# board.net
KiCad netlist of a schematic drawn in EAGLE
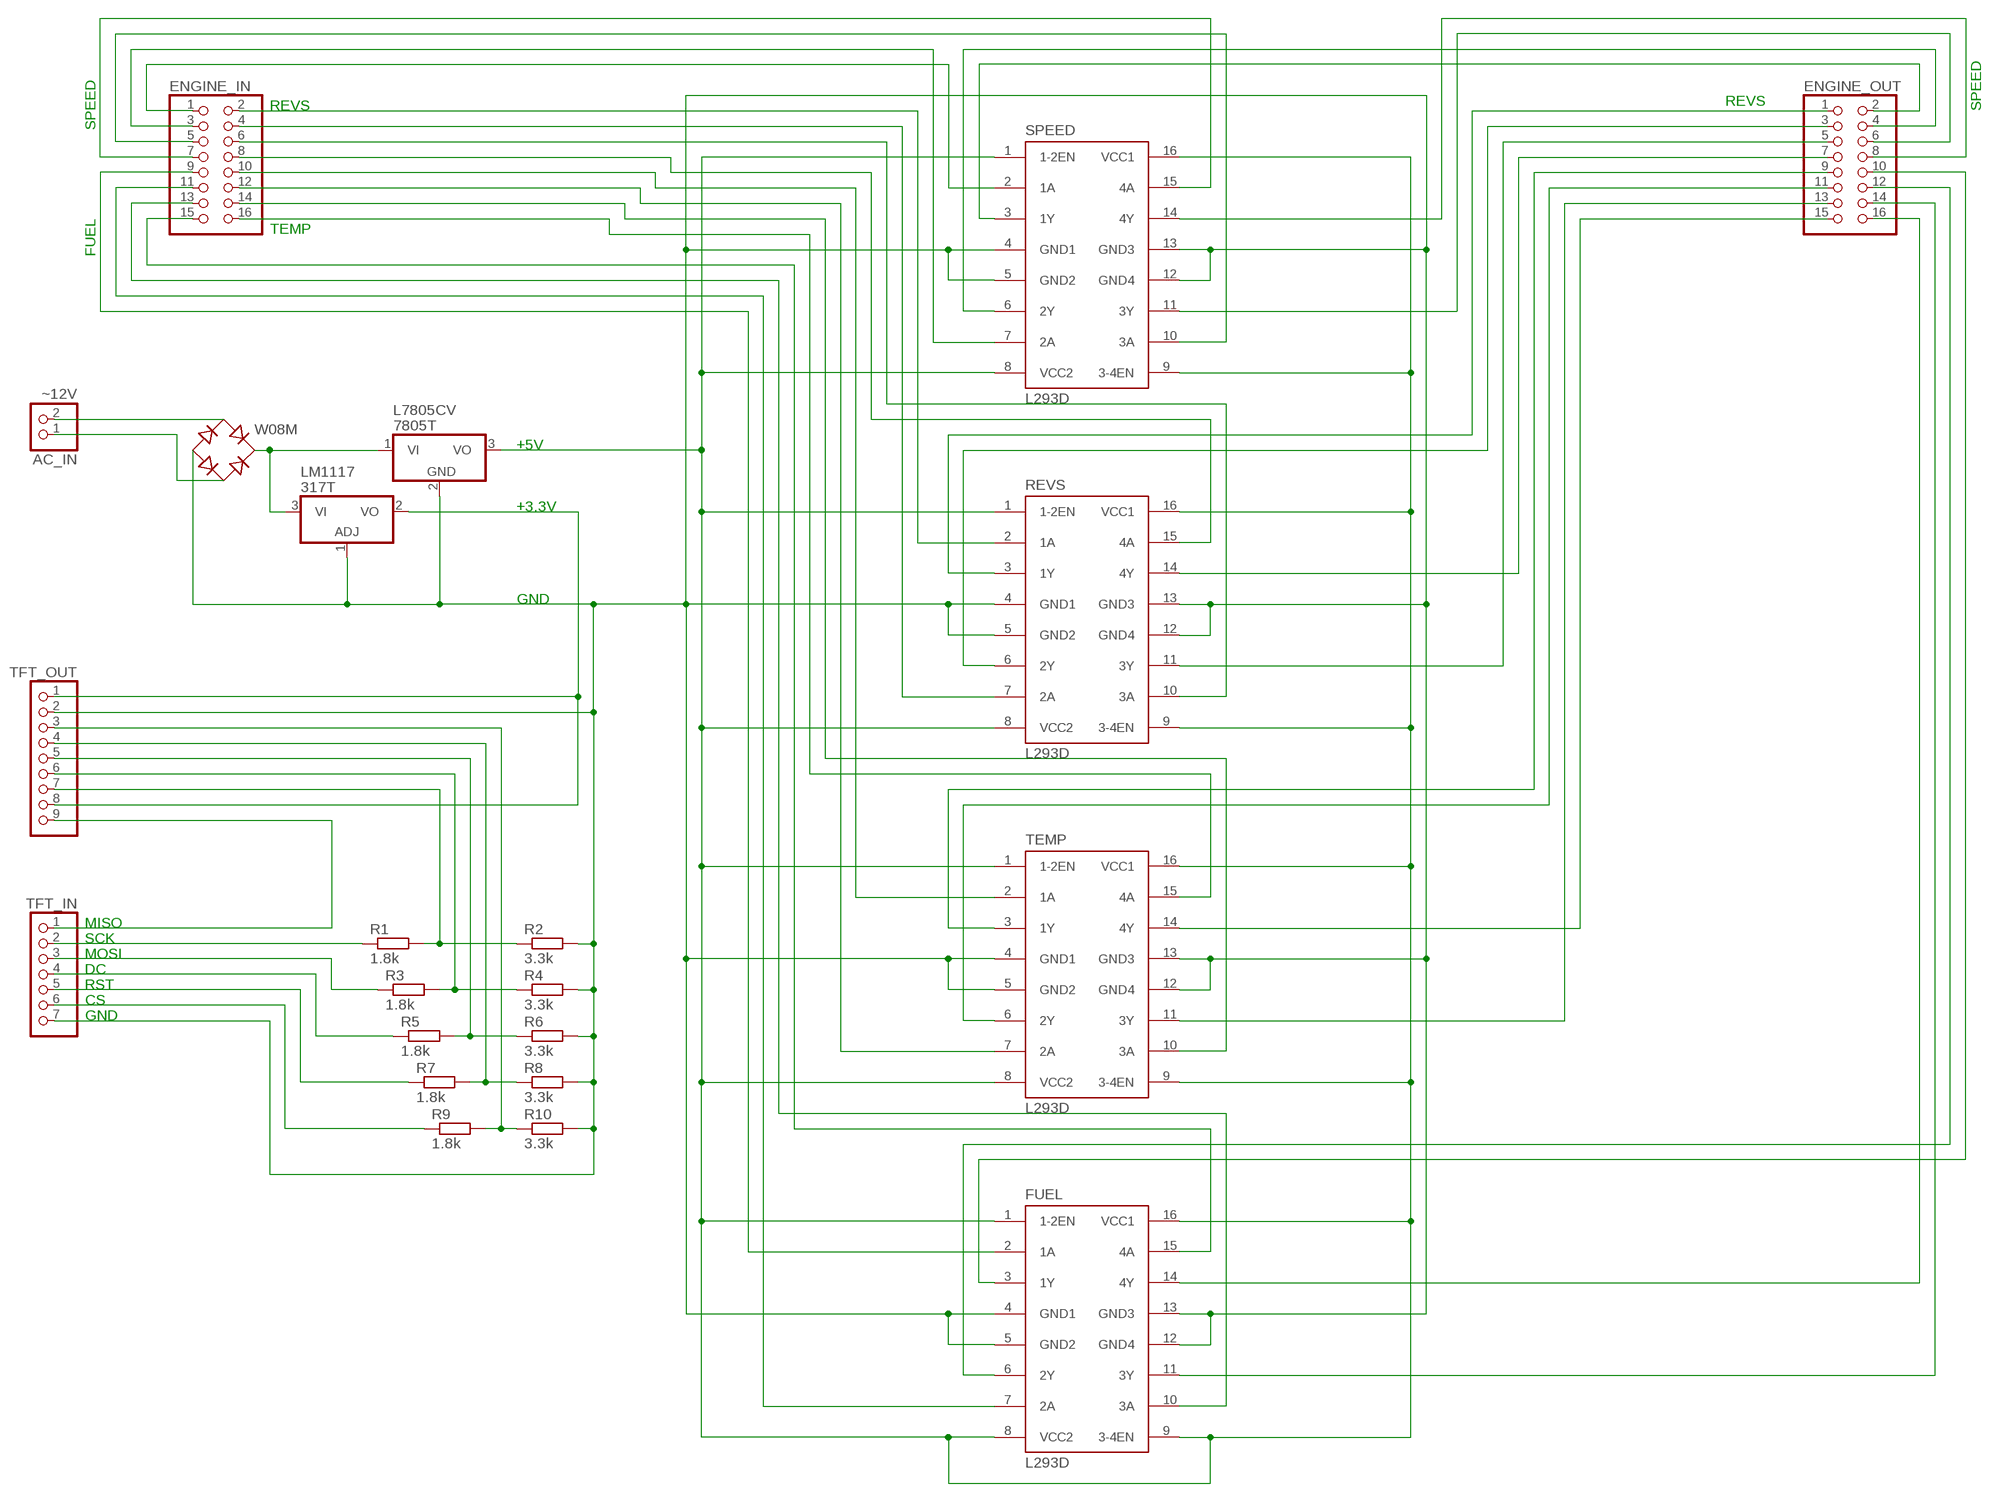
[diagram p0: schematic, sheet 1]

(export (version "E")
  (design (tool "Eeschema 10.0.6"))
  (components
    (comp (ref "AC_IN")
      (value "~12V")
      (footprint "eagle-import:1X02")
      (libsource (lib "eagle-import") (part "PINHD-1X2"))
    )
    (comp (ref "ENGINE_IN")
      (value "PINHD-2X8")
      (footprint "eagle-import:2X08")
      (libsource (lib "eagle-import") (part "PINHD-2X8"))
    )
    (comp (ref "ENGINE_OUT")
      (value "PINHD-2X8")
      (footprint "eagle-import:2X08")
      (libsource (lib "eagle-import") (part "PINHD-2X8"))
    )
    (comp (ref "FUEL")
      (value "L293D")
      (footprint "eagle-import:DIL16")
      (libsource (lib "eagle-import") (part "L293D"))
    )
    (comp (ref "L7805CV")
      (value "7805T")
      (footprint "eagle-import:TO220H")
      (libsource (lib "eagle-import") (part "78T05"))
    )
    (comp (ref "LM1117")
      (value "317T")
      (footprint "eagle-import:TO220H")
      (libsource (lib "eagle-import") (part "317T"))
    )
    (comp (ref "R1")
      (value "1.8k")
      (footprint "eagle-import:0309_12")
      (libsource (lib "eagle-import") (part "R-EU_0309/12"))
    )
    (comp (ref "R2")
      (value "3.3k")
      (footprint "eagle-import:0309_12")
      (libsource (lib "eagle-import") (part "R-EU_0309/12"))
    )
    (comp (ref "R3")
      (value "1.8k")
      (footprint "eagle-import:0309_12")
      (libsource (lib "eagle-import") (part "R-EU_0309/12"))
    )
    (comp (ref "R4")
      (value "3.3k")
      (footprint "eagle-import:0309_12")
      (libsource (lib "eagle-import") (part "R-EU_0309/12"))
    )
    (comp (ref "R5")
      (value "1.8k")
      (footprint "eagle-import:0309_12")
      (libsource (lib "eagle-import") (part "R-EU_0309/12"))
    )
    (comp (ref "R6")
      (value "3.3k")
      (footprint "eagle-import:0309_12")
      (libsource (lib "eagle-import") (part "R-EU_0309/12"))
    )
    (comp (ref "R7")
      (value "1.8k")
      (footprint "eagle-import:0309_12")
      (libsource (lib "eagle-import") (part "R-EU_0309/12"))
    )
    (comp (ref "R8")
      (value "3.3k")
      (footprint "eagle-import:0309_12")
      (libsource (lib "eagle-import") (part "R-EU_0309/12"))
    )
    (comp (ref "R9")
      (value "1.8k")
      (footprint "eagle-import:0309_12")
      (libsource (lib "eagle-import") (part "R-EU_0309/12"))
    )
    (comp (ref "R10")
      (value "3.3k")
      (footprint "eagle-import:0309_12")
      (libsource (lib "eagle-import") (part "R-EU_0309/12"))
    )
    (comp (ref "REVS")
      (value "L293D")
      (footprint "eagle-import:DIL16")
      (libsource (lib "eagle-import") (part "L293D"))
    )
    (comp (ref "SPEED")
      (value "L293D")
      (footprint "eagle-import:DIL16")
      (libsource (lib "eagle-import") (part "L293D"))
    )
    (comp (ref "TEMP")
      (value "L293D")
      (footprint "eagle-import:DIL16")
      (libsource (lib "eagle-import") (part "L293D"))
    )
    (comp (ref "TFT_IN")
      (value "PINHD-1X7")
      (footprint "eagle-import:1X07")
      (libsource (lib "eagle-import") (part "PINHD-1X7"))
    )
    (comp (ref "TFT_OUT")
      (value "PINHD-1X9")
      (footprint "eagle-import:1X09")
      (libsource (lib "eagle-import") (part "PINHD-1X9"))
    )
    (comp (ref "W08M")
      (value "RB1A")
      (footprint "eagle-import:RB1A")
      (libsource (lib "eagle-import") (part "RB1A"))
    )
  )
  (nets
    (net (code "1") (name "Net-(AC_IN-Pad1)") (class "Default")
      (node (ref "AC_IN") (pin "1") (pinfunction "1_1") (pintype "passive"))
      (node (ref "W08M") (pin "AC2") (pinfunction "AC2_AC2") (pintype "passive"))
    )
    (net (code "2") (name "Net-(AC_IN-Pad2)") (class "Default")
      (node (ref "AC_IN") (pin "2") (pinfunction "2_2") (pintype "passive"))
      (node (ref "W08M") (pin "AC1") (pinfunction "AC1_AC1") (pintype "passive"))
    )
    (net (code "3") (name "Net-(FUEL-1-2EN)") (class "Default")
      (node (ref "FUEL") (pin "1") (pinfunction "1-2EN_1") (pintype "input"))
      (node (ref "FUEL") (pin "16") (pinfunction "VCC1_16") (pintype "power_in"))
      (node (ref "FUEL") (pin "8") (pinfunction "VCC2_8") (pintype "power_in"))
      (node (ref "FUEL") (pin "9") (pinfunction "3-4EN_9") (pintype "input"))
      (node (ref "L7805CV") (pin "3") (pinfunction "VO_3") (pintype "passive"))
      (node (ref "REVS") (pin "1") (pinfunction "1-2EN_1") (pintype "input"))
      (node (ref "REVS") (pin "16") (pinfunction "VCC1_16") (pintype "power_in"))
      (node (ref "REVS") (pin "8") (pinfunction "VCC2_8") (pintype "power_in"))
      (node (ref "REVS") (pin "9") (pinfunction "3-4EN_9") (pintype "input"))
      (node (ref "SPEED") (pin "1") (pinfunction "1-2EN_1") (pintype "input"))
      (node (ref "SPEED") (pin "16") (pinfunction "VCC1_16") (pintype "power_in"))
      (node (ref "SPEED") (pin "8") (pinfunction "VCC2_8") (pintype "power_in"))
      (node (ref "SPEED") (pin "9") (pinfunction "3-4EN_9") (pintype "input"))
      (node (ref "TEMP") (pin "1") (pinfunction "1-2EN_1") (pintype "input"))
      (node (ref "TEMP") (pin "16") (pinfunction "VCC1_16") (pintype "power_in"))
      (node (ref "TEMP") (pin "8") (pinfunction "VCC2_8") (pintype "power_in"))
      (node (ref "TEMP") (pin "9") (pinfunction "3-4EN_9") (pintype "input"))
    )
    (net (code "4") (name "Net-(FUEL-1A)") (class "Default")
      (node (ref "ENGINE_IN") (pin "9") (pinfunction "9_9") (pintype "passive"))
      (node (ref "FUEL") (pin "2") (pinfunction "1A_2") (pintype "input"))
    )
    (net (code "5") (name "Net-(FUEL-1Y)") (class "Default")
      (node (ref "ENGINE_OUT") (pin "10") (pinfunction "10_10") (pintype "passive"))
      (node (ref "FUEL") (pin "3") (pinfunction "1Y_3") (pintype "output"))
    )
    (net (code "6") (name "Net-(FUEL-2A)") (class "Default")
      (node (ref "ENGINE_IN") (pin "11") (pinfunction "11_11") (pintype "passive"))
      (node (ref "FUEL") (pin "7") (pinfunction "2A_7") (pintype "input"))
    )
    (net (code "7") (name "Net-(FUEL-2Y)") (class "Default")
      (node (ref "ENGINE_OUT") (pin "12") (pinfunction "12_12") (pintype "passive"))
      (node (ref "FUEL") (pin "6") (pinfunction "2Y_6") (pintype "output"))
    )
    (net (code "8") (name "Net-(FUEL-3A)") (class "Default")
      (node (ref "ENGINE_IN") (pin "13") (pinfunction "13_13") (pintype "passive"))
      (node (ref "FUEL") (pin "10") (pinfunction "3A_10") (pintype "input"))
    )
    (net (code "9") (name "Net-(FUEL-3Y)") (class "Default")
      (node (ref "ENGINE_OUT") (pin "14") (pinfunction "14_14") (pintype "passive"))
      (node (ref "FUEL") (pin "11") (pinfunction "3Y_11") (pintype "output"))
    )
    (net (code "10") (name "Net-(FUEL-4A)") (class "Default")
      (node (ref "ENGINE_IN") (pin "15") (pinfunction "15_15") (pintype "passive"))
      (node (ref "FUEL") (pin "15") (pinfunction "4A_15") (pintype "input"))
    )
    (net (code "11") (name "Net-(FUEL-4Y)") (class "Default")
      (node (ref "ENGINE_OUT") (pin "16") (pinfunction "16_16") (pintype "passive"))
      (node (ref "FUEL") (pin "14") (pinfunction "4Y_14") (pintype "output"))
    )
    (net (code "12") (name "Net-(FUEL-GND1)") (class "Default")
      (node (ref "FUEL") (pin "12") (pinfunction "GND4_12") (pintype "power_in"))
      (node (ref "FUEL") (pin "13") (pinfunction "GND3_13") (pintype "power_in"))
      (node (ref "FUEL") (pin "4") (pinfunction "GND1_4") (pintype "power_in"))
      (node (ref "FUEL") (pin "5") (pinfunction "GND2_5") (pintype "power_in"))
      (node (ref "L7805CV") (pin "2") (pinfunction "GND_2") (pintype "passive"))
      (node (ref "LM1117") (pin "1") (pinfunction "ADJ_1") (pintype "input"))
      (node (ref "R10") (pin "2") (pinfunction "2_2") (pintype "passive"))
      (node (ref "R2") (pin "2") (pinfunction "2_2") (pintype "passive"))
      (node (ref "R4") (pin "2") (pinfunction "2_2") (pintype "passive"))
      (node (ref "R6") (pin "2") (pinfunction "2_2") (pintype "passive"))
      (node (ref "R8") (pin "2") (pinfunction "2_2") (pintype "passive"))
      (node (ref "REVS") (pin "12") (pinfunction "GND4_12") (pintype "power_in"))
      (node (ref "REVS") (pin "13") (pinfunction "GND3_13") (pintype "power_in"))
      (node (ref "REVS") (pin "4") (pinfunction "GND1_4") (pintype "power_in"))
      (node (ref "REVS") (pin "5") (pinfunction "GND2_5") (pintype "power_in"))
      (node (ref "SPEED") (pin "12") (pinfunction "GND4_12") (pintype "power_in"))
      (node (ref "SPEED") (pin "13") (pinfunction "GND3_13") (pintype "power_in"))
      (node (ref "SPEED") (pin "4") (pinfunction "GND1_4") (pintype "power_in"))
      (node (ref "SPEED") (pin "5") (pinfunction "GND2_5") (pintype "power_in"))
      (node (ref "TEMP") (pin "12") (pinfunction "GND4_12") (pintype "power_in"))
      (node (ref "TEMP") (pin "13") (pinfunction "GND3_13") (pintype "power_in"))
      (node (ref "TEMP") (pin "4") (pinfunction "GND1_4") (pintype "power_in"))
      (node (ref "TEMP") (pin "5") (pinfunction "GND2_5") (pintype "power_in"))
      (node (ref "TFT_IN") (pin "7") (pinfunction "7_7") (pintype "passive"))
      (node (ref "TFT_OUT") (pin "2") (pinfunction "2_2") (pintype "passive"))
      (node (ref "W08M") (pin "-") (pinfunction "-_-") (pintype "passive"))
    )
    (net (code "13") (name "Net-(L7805CV-VI)") (class "Default")
      (node (ref "L7805CV") (pin "1") (pinfunction "VI_1") (pintype "input"))
      (node (ref "LM1117") (pin "3") (pinfunction "VI_3") (pintype "input"))
      (node (ref "W08M") (pin "+") (pinfunction "+_+") (pintype "passive"))
    )
    (net (code "14") (name "Net-(LM1117-VO)") (class "Default")
      (node (ref "LM1117") (pin "2") (pinfunction "VO_2") (pintype "passive"))
      (node (ref "TFT_OUT") (pin "1") (pinfunction "1_1") (pintype "passive"))
      (node (ref "TFT_OUT") (pin "8") (pinfunction "8_8") (pintype "passive"))
    )
    (net (code "15") (name "Net-(R1-Pad1)") (class "Default")
      (node (ref "R1") (pin "1") (pinfunction "1_1") (pintype "passive"))
      (node (ref "TFT_IN") (pin "2") (pinfunction "2_2") (pintype "passive"))
    )
    (net (code "16") (name "Net-(R1-Pad2)") (class "Default")
      (node (ref "R1") (pin "2") (pinfunction "2_2") (pintype "passive"))
      (node (ref "R2") (pin "1") (pinfunction "1_1") (pintype "passive"))
      (node (ref "TFT_OUT") (pin "7") (pinfunction "7_7") (pintype "passive"))
    )
    (net (code "17") (name "Net-(R3-Pad1)") (class "Default")
      (node (ref "R3") (pin "1") (pinfunction "1_1") (pintype "passive"))
      (node (ref "TFT_IN") (pin "3") (pinfunction "3_3") (pintype "passive"))
    )
    (net (code "18") (name "Net-(R3-Pad2)") (class "Default")
      (node (ref "R3") (pin "2") (pinfunction "2_2") (pintype "passive"))
      (node (ref "R4") (pin "1") (pinfunction "1_1") (pintype "passive"))
      (node (ref "TFT_OUT") (pin "6") (pinfunction "6_6") (pintype "passive"))
    )
    (net (code "19") (name "Net-(R5-Pad1)") (class "Default")
      (node (ref "R5") (pin "1") (pinfunction "1_1") (pintype "passive"))
      (node (ref "TFT_IN") (pin "4") (pinfunction "4_4") (pintype "passive"))
    )
    (net (code "20") (name "Net-(R5-Pad2)") (class "Default")
      (node (ref "R5") (pin "2") (pinfunction "2_2") (pintype "passive"))
      (node (ref "R6") (pin "1") (pinfunction "1_1") (pintype "passive"))
      (node (ref "TFT_OUT") (pin "5") (pinfunction "5_5") (pintype "passive"))
    )
    (net (code "21") (name "Net-(R7-Pad1)") (class "Default")
      (node (ref "R7") (pin "1") (pinfunction "1_1") (pintype "passive"))
      (node (ref "TFT_IN") (pin "5") (pinfunction "5_5") (pintype "passive"))
    )
    (net (code "22") (name "Net-(R7-Pad2)") (class "Default")
      (node (ref "R7") (pin "2") (pinfunction "2_2") (pintype "passive"))
      (node (ref "R8") (pin "1") (pinfunction "1_1") (pintype "passive"))
      (node (ref "TFT_OUT") (pin "4") (pinfunction "4_4") (pintype "passive"))
    )
    (net (code "23") (name "Net-(R9-Pad1)") (class "Default")
      (node (ref "R9") (pin "1") (pinfunction "1_1") (pintype "passive"))
      (node (ref "TFT_IN") (pin "6") (pinfunction "6_6") (pintype "passive"))
    )
    (net (code "24") (name "Net-(R10-Pad1)") (class "Default")
      (node (ref "R10") (pin "1") (pinfunction "1_1") (pintype "passive"))
      (node (ref "R9") (pin "2") (pinfunction "2_2") (pintype "passive"))
      (node (ref "TFT_OUT") (pin "3") (pinfunction "3_3") (pintype "passive"))
    )
    (net (code "25") (name "Net-(REVS-1A)") (class "Default")
      (node (ref "ENGINE_IN") (pin "2") (pinfunction "2_2") (pintype "passive"))
      (node (ref "REVS") (pin "2") (pinfunction "1A_2") (pintype "input"))
    )
    (net (code "26") (name "Net-(REVS-1Y)") (class "Default")
      (node (ref "ENGINE_OUT") (pin "1") (pinfunction "1_1") (pintype "passive"))
      (node (ref "REVS") (pin "3") (pinfunction "1Y_3") (pintype "output"))
    )
    (net (code "27") (name "Net-(REVS-2A)") (class "Default")
      (node (ref "ENGINE_IN") (pin "4") (pinfunction "4_4") (pintype "passive"))
      (node (ref "REVS") (pin "7") (pinfunction "2A_7") (pintype "input"))
    )
    (net (code "28") (name "Net-(REVS-2Y)") (class "Default")
      (node (ref "ENGINE_OUT") (pin "3") (pinfunction "3_3") (pintype "passive"))
      (node (ref "REVS") (pin "6") (pinfunction "2Y_6") (pintype "output"))
    )
    (net (code "29") (name "Net-(REVS-3A)") (class "Default")
      (node (ref "ENGINE_IN") (pin "6") (pinfunction "6_6") (pintype "passive"))
      (node (ref "REVS") (pin "10") (pinfunction "3A_10") (pintype "input"))
    )
    (net (code "30") (name "Net-(REVS-3Y)") (class "Default")
      (node (ref "ENGINE_OUT") (pin "5") (pinfunction "5_5") (pintype "passive"))
      (node (ref "REVS") (pin "11") (pinfunction "3Y_11") (pintype "output"))
    )
    (net (code "31") (name "Net-(REVS-4A)") (class "Default")
      (node (ref "ENGINE_IN") (pin "8") (pinfunction "8_8") (pintype "passive"))
      (node (ref "REVS") (pin "15") (pinfunction "4A_15") (pintype "input"))
    )
    (net (code "32") (name "Net-(REVS-4Y)") (class "Default")
      (node (ref "ENGINE_OUT") (pin "7") (pinfunction "7_7") (pintype "passive"))
      (node (ref "REVS") (pin "14") (pinfunction "4Y_14") (pintype "output"))
    )
    (net (code "33") (name "Net-(SPEED-1A)") (class "Default")
      (node (ref "ENGINE_IN") (pin "1") (pinfunction "1_1") (pintype "passive"))
      (node (ref "SPEED") (pin "2") (pinfunction "1A_2") (pintype "input"))
    )
    (net (code "34") (name "Net-(SPEED-1Y)") (class "Default")
      (node (ref "ENGINE_OUT") (pin "2") (pinfunction "2_2") (pintype "passive"))
      (node (ref "SPEED") (pin "3") (pinfunction "1Y_3") (pintype "output"))
    )
    (net (code "35") (name "Net-(SPEED-2A)") (class "Default")
      (node (ref "ENGINE_IN") (pin "3") (pinfunction "3_3") (pintype "passive"))
      (node (ref "SPEED") (pin "7") (pinfunction "2A_7") (pintype "input"))
    )
    (net (code "36") (name "Net-(SPEED-2Y)") (class "Default")
      (node (ref "ENGINE_OUT") (pin "4") (pinfunction "4_4") (pintype "passive"))
      (node (ref "SPEED") (pin "6") (pinfunction "2Y_6") (pintype "output"))
    )
    (net (code "37") (name "Net-(SPEED-3A)") (class "Default")
      (node (ref "ENGINE_IN") (pin "5") (pinfunction "5_5") (pintype "passive"))
      (node (ref "SPEED") (pin "10") (pinfunction "3A_10") (pintype "input"))
    )
    (net (code "38") (name "Net-(SPEED-3Y)") (class "Default")
      (node (ref "ENGINE_OUT") (pin "6") (pinfunction "6_6") (pintype "passive"))
      (node (ref "SPEED") (pin "11") (pinfunction "3Y_11") (pintype "output"))
    )
    (net (code "39") (name "Net-(SPEED-4A)") (class "Default")
      (node (ref "ENGINE_IN") (pin "7") (pinfunction "7_7") (pintype "passive"))
      (node (ref "SPEED") (pin "15") (pinfunction "4A_15") (pintype "input"))
    )
    (net (code "40") (name "Net-(SPEED-4Y)") (class "Default")
      (node (ref "ENGINE_OUT") (pin "8") (pinfunction "8_8") (pintype "passive"))
      (node (ref "SPEED") (pin "14") (pinfunction "4Y_14") (pintype "output"))
    )
    (net (code "41") (name "Net-(TEMP-1A)") (class "Default")
      (node (ref "ENGINE_IN") (pin "10") (pinfunction "10_10") (pintype "passive"))
      (node (ref "TEMP") (pin "2") (pinfunction "1A_2") (pintype "input"))
    )
    (net (code "42") (name "Net-(TEMP-1Y)") (class "Default")
      (node (ref "ENGINE_OUT") (pin "9") (pinfunction "9_9") (pintype "passive"))
      (node (ref "TEMP") (pin "3") (pinfunction "1Y_3") (pintype "output"))
    )
    (net (code "43") (name "Net-(TEMP-2A)") (class "Default")
      (node (ref "ENGINE_IN") (pin "12") (pinfunction "12_12") (pintype "passive"))
      (node (ref "TEMP") (pin "7") (pinfunction "2A_7") (pintype "input"))
    )
    (net (code "44") (name "Net-(TEMP-2Y)") (class "Default")
      (node (ref "ENGINE_OUT") (pin "11") (pinfunction "11_11") (pintype "passive"))
      (node (ref "TEMP") (pin "6") (pinfunction "2Y_6") (pintype "output"))
    )
    (net (code "45") (name "Net-(TEMP-3A)") (class "Default")
      (node (ref "ENGINE_IN") (pin "14") (pinfunction "14_14") (pintype "passive"))
      (node (ref "TEMP") (pin "10") (pinfunction "3A_10") (pintype "input"))
    )
    (net (code "46") (name "Net-(TEMP-3Y)") (class "Default")
      (node (ref "ENGINE_OUT") (pin "13") (pinfunction "13_13") (pintype "passive"))
      (node (ref "TEMP") (pin "11") (pinfunction "3Y_11") (pintype "output"))
    )
    (net (code "47") (name "Net-(TEMP-4A)") (class "Default")
      (node (ref "ENGINE_IN") (pin "16") (pinfunction "16_16") (pintype "passive"))
      (node (ref "TEMP") (pin "15") (pinfunction "4A_15") (pintype "input"))
    )
    (net (code "48") (name "Net-(TEMP-4Y)") (class "Default")
      (node (ref "ENGINE_OUT") (pin "15") (pinfunction "15_15") (pintype "passive"))
      (node (ref "TEMP") (pin "14") (pinfunction "4Y_14") (pintype "output"))
    )
    (net (code "49") (name "Net-(TFT_IN-Pad1)") (class "Default")
      (node (ref "TFT_IN") (pin "1") (pinfunction "1_1") (pintype "passive"))
      (node (ref "TFT_OUT") (pin "9") (pinfunction "9_9") (pintype "passive"))
    )
  )
)
